# test_reg.net
KiCad netlist of a schematic drawn in EAGLE
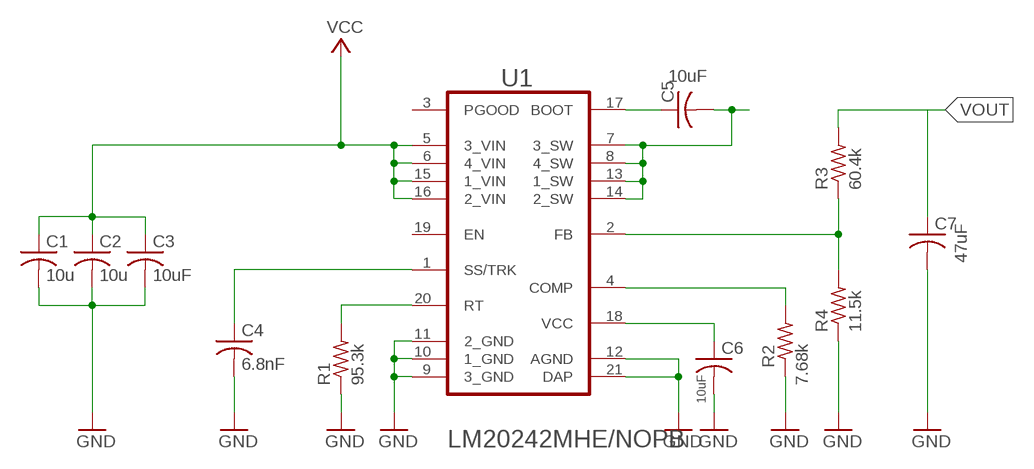
[diagram p0: schematic, sheet 1]

(export (version "E")
  (design (tool "Eeschema 10.0.6"))
  (components
    (comp (ref "C1")
      (value "10u")
      (footprint "eagle-import:C0805")
      (libsource (lib "eagle-import") (part "C-USC0805"))
    )
    (comp (ref "C2")
      (value "10u")
      (footprint "eagle-import:C0805")
      (libsource (lib "eagle-import") (part "C-USC0805"))
    )
    (comp (ref "C3")
      (value "10uF")
      (footprint "eagle-import:C0805")
      (libsource (lib "eagle-import") (part "C-USC0805"))
    )
    (comp (ref "C4")
      (value "6.8nF")
      (footprint "eagle-import:C0805")
      (libsource (lib "eagle-import") (part "C-USC0805"))
    )
    (comp (ref "C5")
      (value "10uF")
      (footprint "eagle-import:C0805")
      (libsource (lib "eagle-import") (part "C-USC0805"))
    )
    (comp (ref "C6")
      (value "10uF")
      (footprint "eagle-import:C0805")
      (libsource (lib "eagle-import") (part "C-USC0805"))
    )
    (comp (ref "C7")
      (value "47uF")
      (footprint "eagle-import:C0805")
      (libsource (lib "eagle-import") (part "C-USC0805"))
    )
    (comp (ref "R1")
      (value "95.3k")
      (footprint "eagle-import:R0805")
      (libsource (lib "eagle-import") (part "R-US_R0805"))
    )
    (comp (ref "R2")
      (value "7.68k")
      (footprint "eagle-import:R0805")
      (libsource (lib "eagle-import") (part "R-US_R0805"))
    )
    (comp (ref "R3")
      (value "60.4k")
      (footprint "eagle-import:R0805")
      (libsource (lib "eagle-import") (part "R-US_R0805"))
    )
    (comp (ref "R4")
      (value "11.5k")
      (footprint "eagle-import:R0805")
      (libsource (lib "eagle-import") (part "R-US_R0805"))
    )
    (comp (ref "U1")
      (value "TI_NATIONAL_SEMICONDUCTOR_LM20242MHE-NOPBTI_NATIONAL_SEMICONDUCTOR_LM20242MHE-NOPB_0_0")
      (footprint "eagle-import:TI_NATIONAL_SEMICONDUCTOR_LM20242MHE-NOPB_0")
      (fields (field (name "MF") "TI National Semiconductor") (field (name "MPN") "LM20242MHE/NOPB"))
      (libsource (lib "eagle-import") (part "TI_NATIONAL_SEMICONDUCTOR_LM20242MHE-NOPBTI_NATIONAL_SEMICONDUCTOR_LM20242MHE-NOPB_0_0"))
    )
  )
  (nets
    (net (code "1") (name "GND") (class "Default")
      (node (ref "C1") (pin "2") (pinfunction "2_2") (pintype "passive"))
      (node (ref "C2") (pin "2") (pinfunction "2_2") (pintype "passive"))
      (node (ref "C3") (pin "2") (pinfunction "2_2") (pintype "passive"))
      (node (ref "C4") (pin "2") (pinfunction "2_2") (pintype "passive"))
      (node (ref "C6") (pin "2") (pinfunction "2_2") (pintype "passive"))
      (node (ref "C7") (pin "2") (pinfunction "2_2") (pintype "passive"))
      (node (ref "R1") (pin "1") (pinfunction "1_1") (pintype "passive"))
      (node (ref "R2") (pin "1") (pinfunction "1_1") (pintype "passive"))
      (node (ref "R4") (pin "1") (pinfunction "1_1") (pintype "passive"))
      (node (ref "U1") (pin "10") (pinfunction "1_GND_10") (pintype "power_in"))
      (node (ref "U1") (pin "11") (pinfunction "2_GND_11") (pintype "power_in"))
      (node (ref "U1") (pin "12") (pinfunction "AGND_12") (pintype "power_in"))
      (node (ref "U1") (pin "21") (pinfunction "DAP_21") (pintype "power_in"))
      (node (ref "U1") (pin "9") (pinfunction "3_GND_9") (pintype "power_in"))
    )
    (net (code "2") (name "Net-(U1-1_SW)") (class "Default")
      (node (ref "C5") (pin "2") (pinfunction "2_2") (pintype "passive"))
      (node (ref "U1") (pin "13") (pinfunction "1_SW_13") (pintype "power_in"))
      (node (ref "U1") (pin "14") (pinfunction "2_SW_14") (pintype "power_in"))
      (node (ref "U1") (pin "7") (pinfunction "3_SW_7") (pintype "power_in"))
      (node (ref "U1") (pin "8") (pinfunction "4_SW_8") (pintype "power_in"))
    )
    (net (code "3") (name "Net-(U1-BOOT)") (class "Default")
      (node (ref "C5") (pin "1") (pinfunction "1_1") (pintype "passive"))
      (node (ref "U1") (pin "17") (pinfunction "BOOT_17") (pintype "passive"))
    )
    (net (code "4") (name "Net-(U1-COMP)") (class "Default")
      (node (ref "R2") (pin "2") (pinfunction "2_2") (pintype "passive"))
      (node (ref "U1") (pin "4") (pinfunction "COMP_4") (pintype "passive"))
    )
    (net (code "5") (name "Net-(U1-FB)") (class "Default")
      (node (ref "R3") (pin "1") (pinfunction "1_1") (pintype "passive"))
      (node (ref "R4") (pin "2") (pinfunction "2_2") (pintype "passive"))
      (node (ref "U1") (pin "2") (pinfunction "FB_2") (pintype "input"))
    )
    (net (code "6") (name "Net-(U1-RT)") (class "Default")
      (node (ref "R1") (pin "2") (pinfunction "2_2") (pintype "passive"))
      (node (ref "U1") (pin "20") (pinfunction "RT_20") (pintype "input"))
    )
    (net (code "7") (name "Net-(U1-SS{slash}TRK)") (class "Default")
      (node (ref "C4") (pin "1") (pinfunction "1_1") (pintype "passive"))
      (node (ref "U1") (pin "1") (pinfunction "SS/TRK_1") (pintype "passive"))
    )
    (net (code "8") (name "Net-(U1-VCC)") (class "Default")
      (node (ref "C6") (pin "1") (pinfunction "1_1") (pintype "passive"))
      (node (ref "U1") (pin "18") (pinfunction "VCC_18") (pintype "power_in"))
    )
    (net (code "9") (name "VCC") (class "Default")
      (node (ref "C1") (pin "1") (pinfunction "1_1") (pintype "passive"))
      (node (ref "C2") (pin "1") (pinfunction "1_1") (pintype "passive"))
      (node (ref "C3") (pin "1") (pinfunction "1_1") (pintype "passive"))
      (node (ref "U1") (pin "15") (pinfunction "1_VIN_15") (pintype "power_in"))
      (node (ref "U1") (pin "16") (pinfunction "2_VIN_16") (pintype "power_in"))
      (node (ref "U1") (pin "5") (pinfunction "3_VIN_5") (pintype "power_in"))
      (node (ref "U1") (pin "6") (pinfunction "4_VIN_6") (pintype "power_in"))
    )
    (net (code "10") (name "VOUT") (class "Default")
      (node (ref "C7") (pin "1") (pinfunction "1_1") (pintype "passive"))
      (node (ref "R3") (pin "2") (pinfunction "2_2") (pintype "passive"))
    )
    (net (code "11") (name "unconnected-(U1-EN-Pad19)") (class "Default")
      (node (ref "U1") (pin "19") (pinfunction "EN_19") (pintype "passive"))
    )
    (net (code "12") (name "unconnected-(U1-PGOOD-Pad3)") (class "Default")
      (node (ref "U1") (pin "3") (pinfunction "PGOOD_3") (pintype "open_collector"))
    )
  )
)
